# Power_Path.net
KiCad netlist of a schematic drawn in Altium Designer
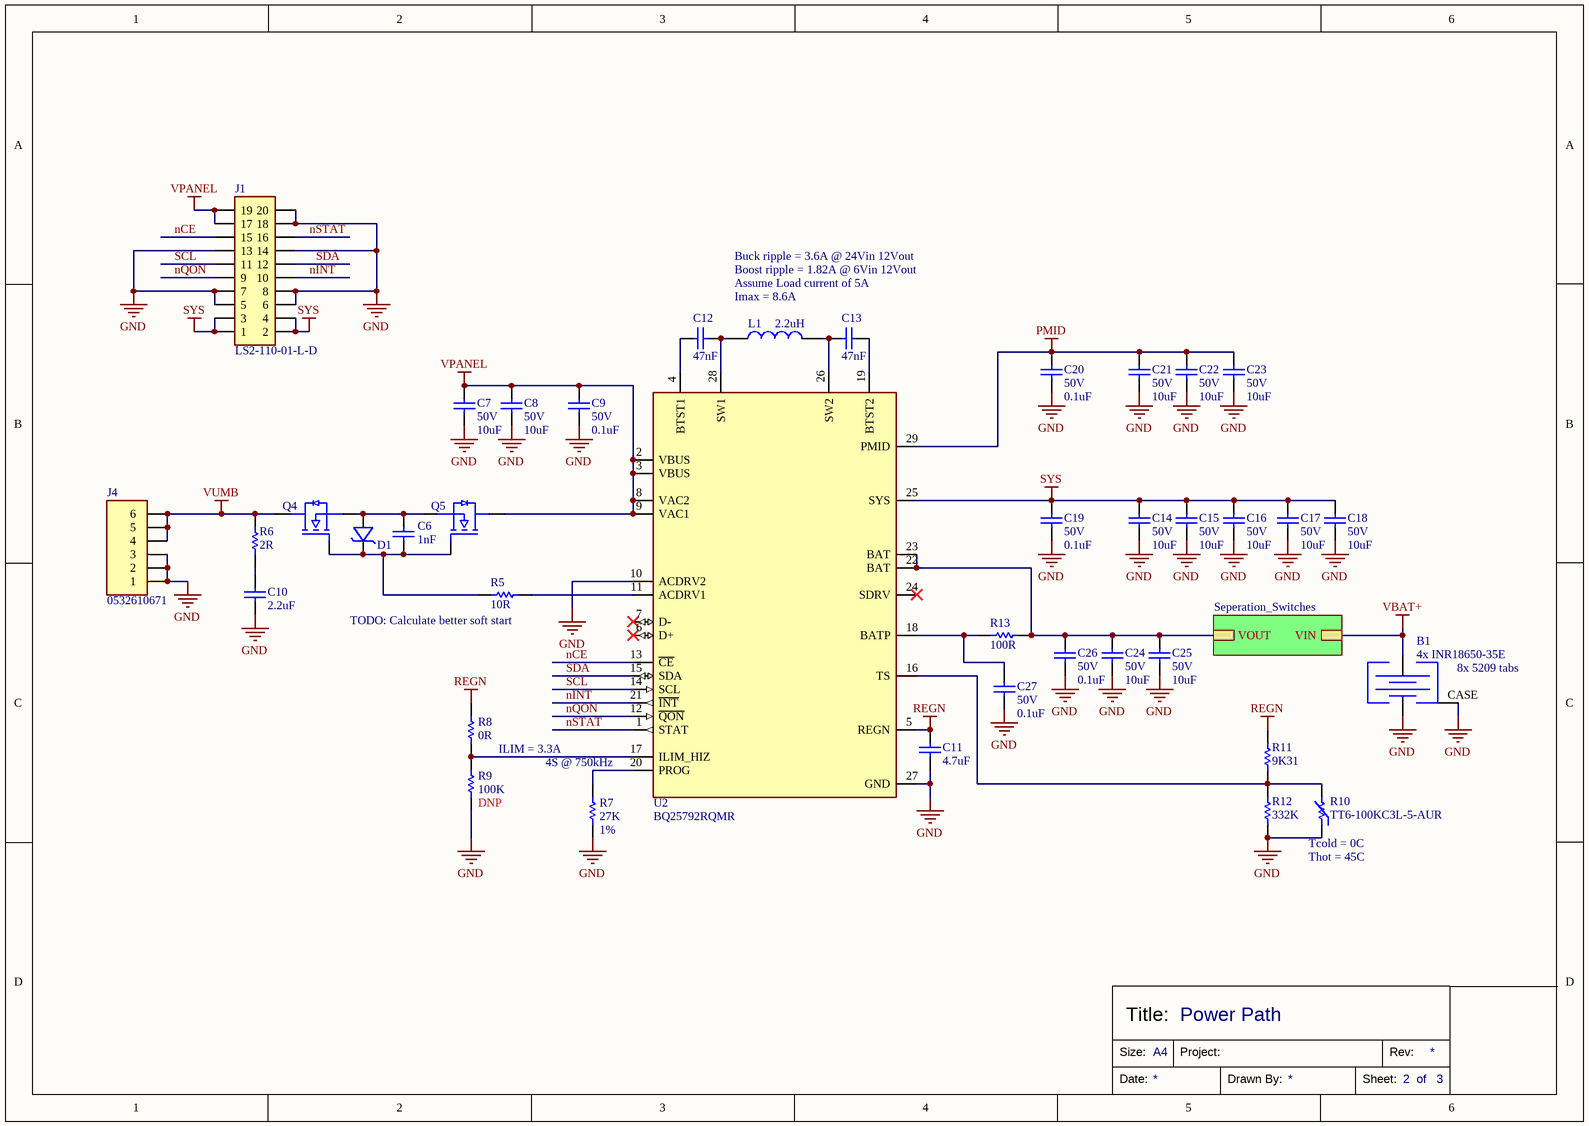
[diagram p0: Power_Path.SchDoc]

(export (version "E")
  (design (tool "Eeschema 10.0.6"))
  (components
    (comp (ref "B1")
      (value "4x INR18650-35E")
      (footprint "4S Battery")
      (description "Custom 4S battery component for Cubesat EPS")
      (libsource (lib "Ahristi_Library") (part "4S Battery"))
    )
    (comp (ref "C6")
      (value "GRM1885C1H102JA01D")
      (footprint "CAPC0603X040")
      (description "1nF ±5% 50V Ceramic Capacitor C0G, NP0 0603 (1608 Metric)")
      (fields
        (field (name "TOLERANCE") "5%")
        (field (name "DISTRIBUTOR PART NUMBER") "490-1451-1-ND")
        (field (name "CAPACITANCE") "1nF")
      )
      (libsource (lib "Ahristi_Library") (part "GRM1885C1H102JA01D"))
    )
    (comp (ref "C7")
      (value "CL32B106KBJNNNE")
      (footprint "CAPC1210X090")
      (description "10 µF ±10% 50V Ceramic Capacitor X7R 1210 (3225 Metric)")
      (fields
        (field (name "DISTRIBUTOR PART NUMBER") "1276-3387-1-ND")
        (field (name "TOLERANCE") "10%")
        (field (name "VOLTAGE RATING") "50V")
        (field (name "CAPACITANCE") "10uF")
      )
      (libsource (lib "Ahristi_Library") (part "CL32B106KBJNNNE"))
    )
    (comp (ref "C8")
      (value "CL32B106KBJNNNE")
      (footprint "CAPC1210X090")
      (description "10 µF ±10% 50V Ceramic Capacitor X7R 1210 (3225 Metric)")
      (fields
        (field (name "DISTRIBUTOR PART NUMBER") "1276-3387-1-ND")
        (field (name "TOLERANCE") "10%")
        (field (name "VOLTAGE RATING") "50V")
        (field (name "CAPACITANCE") "10uF")
      )
      (libsource (lib "Ahristi_Library") (part "CL32B106KBJNNNE"))
    )
    (comp (ref "C9")
      (value "CL05B104KB5NNNC")
      (footprint "CAPC0402X020")
      (description "0.1 µF ±10% 50V Ceramic Capacitor X7R 0402 (1005 Metric)")
      (fields
        (field (name "TOLERANCE") "10%")
        (field (name "DISTRIBUTOR PART NUMBER") "1276-CL05B104KB5NNNCCT-ND")
        (field (name "VOLTAGE RATING") "50V")
        (field (name "CAPACITANCE") "0.1uF")
      )
      (libsource (lib "Ahristi_Library") (part "CL05B104KB5NNNC"))
    )
    (comp (ref "C10")
      (value "CL21A225KBFNNNE")
      (footprint "CAPC0805X060")
      (description "2.2uF ±10% 25V Ceramic Capacitor X7R 0805 (2012 Metric)")
      (fields
        (field (name "DISTRIBUTOR PART NUMBER") "1276-6702-1-ND")
        (field (name "TOLERANCE") "10%")
        (field (name "CAPACITANCE") "2.2uF")
      )
      (libsource (lib "Ahristi_Library") (part "CL21A225KBFNNNE"))
    )
    (comp (ref "C11")
      (value "CL21A475KAQNNNE")
      (footprint "CAPC0805X060")
      (description "4.7 µF ±10% 25V Ceramic Capacitor X5R 0805 (2012 Metric)")
      (fields
        (field (name "DISTRIBUTOR PART NUMBER") "1276-1244-1-ND")
        (field (name "TOLERANCE") "10%")
        (field (name "CAPACITANCE") "4.7uF")
      )
      (libsource (lib "Ahristi_Library") (part "CL21A475KAQNNNE"))
    )
    (comp (ref "C12")
      (value "C0603C473K1RACTU")
      (footprint "CAPC0603X040")
      (description "0.047 µF ±10% 100V Ceramic Capacitor X7R 0603 (1608 Metric)")
      (fields
        (field (name "DISTRIBUTOR PART NUMBER") "399-C0603C473K1RACTUCT-ND")
        (field (name "TOLERANCE") "10%")
        (field (name "CAPACITANCE") "47nF")
      )
      (libsource (lib "Ahristi_Library") (part "C0603C473K1RACTU"))
    )
    (comp (ref "C13")
      (value "C0603C473K1RACTU")
      (footprint "CAPC0603X040")
      (description "0.047 µF ±10% 100V Ceramic Capacitor X7R 0603 (1608 Metric)")
      (fields
        (field (name "DISTRIBUTOR PART NUMBER") "399-C0603C473K1RACTUCT-ND")
        (field (name "TOLERANCE") "10%")
        (field (name "CAPACITANCE") "47nF")
      )
      (libsource (lib "Ahristi_Library") (part "C0603C473K1RACTU"))
    )
    (comp (ref "C14")
      (value "CL32B106KBJNNNE")
      (footprint "CAPC1210X090")
      (description "10 µF ±10% 50V Ceramic Capacitor X7R 1210 (3225 Metric)")
      (fields
        (field (name "DISTRIBUTOR PART NUMBER") "1276-3387-1-ND")
        (field (name "TOLERANCE") "10%")
        (field (name "VOLTAGE RATING") "50V")
        (field (name "CAPACITANCE") "10uF")
      )
      (libsource (lib "Ahristi_Library") (part "CL32B106KBJNNNE"))
    )
    (comp (ref "C15")
      (value "CL32B106KBJNNNE")
      (footprint "CAPC1210X090")
      (description "10 µF ±10% 50V Ceramic Capacitor X7R 1210 (3225 Metric)")
      (fields
        (field (name "DISTRIBUTOR PART NUMBER") "1276-3387-1-ND")
        (field (name "TOLERANCE") "10%")
        (field (name "VOLTAGE RATING") "50V")
        (field (name "CAPACITANCE") "10uF")
      )
      (libsource (lib "Ahristi_Library") (part "CL32B106KBJNNNE"))
    )
    (comp (ref "C16")
      (value "CL32B106KBJNNNE")
      (footprint "CAPC1210X090")
      (description "10 µF ±10% 50V Ceramic Capacitor X7R 1210 (3225 Metric)")
      (fields
        (field (name "DISTRIBUTOR PART NUMBER") "1276-3387-1-ND")
        (field (name "TOLERANCE") "10%")
        (field (name "VOLTAGE RATING") "50V")
        (field (name "CAPACITANCE") "10uF")
      )
      (libsource (lib "Ahristi_Library") (part "CL32B106KBJNNNE"))
    )
    (comp (ref "C17")
      (value "CL32B106KBJNNNE")
      (footprint "CAPC1210X090")
      (description "10 µF ±10% 50V Ceramic Capacitor X7R 1210 (3225 Metric)")
      (fields
        (field (name "DISTRIBUTOR PART NUMBER") "1276-3387-1-ND")
        (field (name "TOLERANCE") "10%")
        (field (name "VOLTAGE RATING") "50V")
        (field (name "CAPACITANCE") "10uF")
      )
      (libsource (lib "Ahristi_Library") (part "CL32B106KBJNNNE"))
    )
    (comp (ref "C18")
      (value "CL32B106KBJNNNE")
      (footprint "CAPC1210X090")
      (description "10 µF ±10% 50V Ceramic Capacitor X7R 1210 (3225 Metric)")
      (fields
        (field (name "DISTRIBUTOR PART NUMBER") "1276-3387-1-ND")
        (field (name "TOLERANCE") "10%")
        (field (name "VOLTAGE RATING") "50V")
        (field (name "CAPACITANCE") "10uF")
      )
      (libsource (lib "Ahristi_Library") (part "CL32B106KBJNNNE"))
    )
    (comp (ref "C19")
      (value "CL05B104KB5NNNC")
      (footprint "CAPC0402X020")
      (description "0.1 µF ±10% 50V Ceramic Capacitor X7R 0402 (1005 Metric)")
      (fields
        (field (name "TOLERANCE") "10%")
        (field (name "DISTRIBUTOR PART NUMBER") "1276-CL05B104KB5NNNCCT-ND")
        (field (name "VOLTAGE RATING") "50V")
        (field (name "CAPACITANCE") "0.1uF")
      )
      (libsource (lib "Ahristi_Library") (part "CL05B104KB5NNNC"))
    )
    (comp (ref "C20")
      (value "CL05B104KB5NNNC")
      (footprint "CAPC0402X020")
      (description "0.1 µF ±10% 50V Ceramic Capacitor X7R 0402 (1005 Metric)")
      (fields
        (field (name "TOLERANCE") "10%")
        (field (name "DISTRIBUTOR PART NUMBER") "1276-CL05B104KB5NNNCCT-ND")
        (field (name "VOLTAGE RATING") "50V")
        (field (name "CAPACITANCE") "0.1uF")
      )
      (libsource (lib "Ahristi_Library") (part "CL05B104KB5NNNC"))
    )
    (comp (ref "C21")
      (value "CL32B106KBJNNNE")
      (footprint "CAPC1210X090")
      (description "10 µF ±10% 50V Ceramic Capacitor X7R 1210 (3225 Metric)")
      (fields
        (field (name "DISTRIBUTOR PART NUMBER") "1276-3387-1-ND")
        (field (name "TOLERANCE") "10%")
        (field (name "VOLTAGE RATING") "50V")
        (field (name "CAPACITANCE") "10uF")
      )
      (libsource (lib "Ahristi_Library") (part "CL32B106KBJNNNE"))
    )
    (comp (ref "C22")
      (value "CL32B106KBJNNNE")
      (footprint "CAPC1210X090")
      (description "10 µF ±10% 50V Ceramic Capacitor X7R 1210 (3225 Metric)")
      (fields
        (field (name "DISTRIBUTOR PART NUMBER") "1276-3387-1-ND")
        (field (name "TOLERANCE") "10%")
        (field (name "VOLTAGE RATING") "50V")
        (field (name "CAPACITANCE") "10uF")
      )
      (libsource (lib "Ahristi_Library") (part "CL32B106KBJNNNE"))
    )
    (comp (ref "C23")
      (value "CL32B106KBJNNNE")
      (footprint "CAPC1210X090")
      (description "10 µF ±10% 50V Ceramic Capacitor X7R 1210 (3225 Metric)")
      (fields
        (field (name "DISTRIBUTOR PART NUMBER") "1276-3387-1-ND")
        (field (name "TOLERANCE") "10%")
        (field (name "VOLTAGE RATING") "50V")
        (field (name "CAPACITANCE") "10uF")
      )
      (libsource (lib "Ahristi_Library") (part "CL32B106KBJNNNE"))
    )
    (comp (ref "C24")
      (value "CL32B106KBJNNNE")
      (footprint "CAPC1210X090")
      (description "10 µF ±10% 50V Ceramic Capacitor X7R 1210 (3225 Metric)")
      (fields
        (field (name "DISTRIBUTOR PART NUMBER") "1276-3387-1-ND")
        (field (name "TOLERANCE") "10%")
        (field (name "VOLTAGE RATING") "50V")
        (field (name "CAPACITANCE") "10uF")
      )
      (libsource (lib "Ahristi_Library") (part "CL32B106KBJNNNE"))
    )
    (comp (ref "C25")
      (value "CL32B106KBJNNNE")
      (footprint "CAPC1210X090")
      (description "10 µF ±10% 50V Ceramic Capacitor X7R 1210 (3225 Metric)")
      (fields
        (field (name "DISTRIBUTOR PART NUMBER") "1276-3387-1-ND")
        (field (name "TOLERANCE") "10%")
        (field (name "VOLTAGE RATING") "50V")
        (field (name "CAPACITANCE") "10uF")
      )
      (libsource (lib "Ahristi_Library") (part "CL32B106KBJNNNE"))
    )
    (comp (ref "C26")
      (value "CL05B104KB5NNNC")
      (footprint "CAPC0402X020")
      (description "0.1 µF ±10% 50V Ceramic Capacitor X7R 0402 (1005 Metric)")
      (fields
        (field (name "TOLERANCE") "10%")
        (field (name "DISTRIBUTOR PART NUMBER") "1276-CL05B104KB5NNNCCT-ND")
        (field (name "VOLTAGE RATING") "50V")
        (field (name "CAPACITANCE") "0.1uF")
      )
      (libsource (lib "Ahristi_Library") (part "CL05B104KB5NNNC"))
    )
    (comp (ref "C27")
      (value "CL05B104KB5NNNC")
      (footprint "CAPC0402X020")
      (description "0.1 µF ±10% 50V Ceramic Capacitor X7R 0402 (1005 Metric)")
      (fields
        (field (name "TOLERANCE") "10%")
        (field (name "DISTRIBUTOR PART NUMBER") "1276-CL05B104KB5NNNCCT-ND")
        (field (name "VOLTAGE RATING") "50V")
        (field (name "CAPACITANCE") "0.1uF")
      )
      (libsource (lib "Ahristi_Library") (part "CL05B104KB5NNNC"))
    )
    (comp (ref "D1")
      (value "BZT52C12T-7")
      (footprint "SOD-523")
      (description "Zener Diode 12 V 300 mW ±5% Surface Mount SOD-523")
      (fields (field (name "DISTRIBUTOR PART NUMBER") "BZT52C12T-7DICT-ND"))
      (libsource (lib "Ahristi_Library") (part "BZT52C12T-7"))
    )
    (comp (ref "J1")
      (value "LS2-110-01-L-D")
      (footprint "LS2-110-01-L-D")
      (description "Connector Self Mating 20 Position , Non-Gendered, Hermaphroditic Through Hole Gold")
      (fields (field (name "DISTRIBUTOR PART NUMBER") "SAM9665-ND"))
      (libsource (lib "Ahristi_Library") (part "LS2-110-01-L-D"))
    )
    (comp (ref "J4")
      (value "0532610671")
      (footprint "0532610671")
      (description "Connector Header Surface Mount, Right Angle 6 position 0.049\" (1.25mm) Picoblade")
      (fields (field (name "DISTRIBUTOR PART NUMBER") "WM7624CT-ND"))
      (libsource (lib "Ahristi_Library") (part "0532610671"))
    )
    (comp (ref "L1")
      (value "SPM7054VT-2R2M-D")
      (footprint "SPM7054VT-2R2M-D")
      (description "2.2 µH Shielded Drum Core, Wirewound Inductor 12 A 7.4mOhm Nonstandard")
      (fields
        (field (name "DISTRIBUTOR PART NUMBER") "445-SPM7054VT-2R2M-DCT-ND")
        (field (name "INDUCTANCE") "2.2uH")
        (field (name "TOLERANCE") "20%")
      )
      (libsource (lib "Ahristi_Library") (part "SPM7054VT-2R2M-D"))
    )
    (comp (ref "Q4")
      (value "CSD18511Q5A")
      (footprint "CSD18511Q5A")
      (description "40-V, N channel NexFET™ power MOSFET, single SON 5 mm x 6 mm, 2.3 mOhm")
      (fields (field (name "DISTRIBUTOR PART NUMBER") "296-48119-1-ND"))
      (libsource (lib "Ahristi_Library") (part "CSD18511Q5A"))
    )
    (comp (ref "Q5")
      (value "CSD18511Q5A")
      (footprint "CSD18511Q5A")
      (description "40-V, N channel NexFET™ power MOSFET, single SON 5 mm x 6 mm, 2.3 mOhm")
      (fields (field (name "DISTRIBUTOR PART NUMBER") "296-48119-1-ND"))
      (libsource (lib "Ahristi_Library") (part "CSD18511Q5A"))
    )
    (comp (ref "R5")
      (value "RMCF0603FT10R0")
      (footprint "RESC0603")
      (description "10 Ohms ±1% 0.1W, 1/10W Chip Resistor 0603 (1608 Metric) Automotive AEC-Q200 Thick Film")
      (fields
        (field (name "TOLERANCE") "1%")
        (field (name "DISTRIBUTOR PART NUMBER") "RMCF0603FT10R0CT-ND")
        (field (name "RESISTANCE") "10R")
      )
      (libsource (lib "Ahristi_Library") (part "RMCF0603FT10R0"))
    )
    (comp (ref "R6")
      (value "RMCF0603FT2R00")
      (footprint "RESC0603")
      (fields
        (field (name "TOLERANCE") "1%")
        (field (name "DISTRIBUTOR PART NUMBER") "RMCF0603FT2R00CT-ND")
        (field (name "RESISTANCE") "2R")
      )
      (libsource (lib "Ahristi_Library") (part "RMCF0603FT2R00"))
    )
    (comp (ref "R7")
      (value "RMCF0603FT27K0")
      (footprint "RESC0603")
      (description "27 kOhms ±1% 0.1W, 1/10W Chip Resistor 0603 (1608 Metric) Automotive AEC-Q200 Thick Film")
      (fields
        (field (name "TOLERANCE") "1%")
        (field (name "DISTRIBUTOR PART NUMBER") "RMCF0603FT27K0CT-ND")
        (field (name "RESISTANCE") "27K")
      )
      (libsource (lib "Ahristi_Library") (part "RMCF0603FT27K0"))
    )
    (comp (ref "R8")
      (value "RMCF0805ZT0R00")
      (footprint "RESC0805")
      (description "0 Ohms Jumper Chip Resistor 0805 (2012 Metric) Automotive AEC-Q200 Thick Film")
      (fields
        (field (name "TOLERANCE") "1%")
        (field (name "DISTRIBUTOR PART NUMBER") "RMCF0805ZT0R00CT-ND")
        (field (name "RESISTANCE") "0R")
      )
      (libsource (lib "Ahristi_Library") (part "RMCF0805ZT0R00"))
    )
    (comp (ref "R9")
      (value "RMCF0805FG100K")
      (footprint "RESC0805")
      (description "100 kOhms ±1% 0.125W, 1/8W Chip Resistor 0805 (2012 Metric) Automotive AEC-Q200 Thick Film")
      (fields
        (field (name "TOLERANCE") "1%")
        (field (name "DISTRIBUTOR PART NUMBER") "RMCF0805FG100KCT-ND")
        (field (name "RESISTANCE") "100K")
      )
      (libsource (lib "Ahristi_Library") (part "RMCF0805FG100K"))
    )
    (comp (ref "R10")
      (value "TT6-100KC3L-5-AUR")
      (footprint "TT6-10KC8-9-25")
      (description "NTC Thermistor 10k Probe")
      (fields (field (name "DISTRIBUTOR PART NUMBER") "1912-TT6-10KC8-9-25-ND"))
      (libsource (lib "Ahristi_Library") (part "TT6-100KC3L-5-AUR"))
    )
    (comp (ref "R11")
      (value "RMCF0805FT9K31")
      (footprint "RESC0805")
      (description "9.31 kOhms ±1% 0.125W, 1/8W Chip Resistor 0805 (2012 Metric) Automotive AEC-Q200 Thick Film")
      (fields
        (field (name "TOLERANCE") "1%")
        (field (name "DISTRIBUTOR PART NUMBER") "738-RMCF0805FT9K31CT-ND")
        (field (name "RESISTANCE") "9K31")
      )
      (libsource (lib "Ahristi_Library") (part "RMCF0805FT9K31"))
    )
    (comp (ref "R12")
      (value "RMCF0805FT332K")
      (footprint "RESC0805")
      (description "332 kOhms ±1% 0.125W, 1/8W Chip Resistor 0805 (2012 Metric) Automotive AEC-Q200 Thick Film")
      (fields
        (field (name "TOLERANCE") "1%")
        (field (name "DISTRIBUTOR PART NUMBER") "RMCF0805FT332KCT-ND")
        (field (name "RESISTANCE") "332K")
      )
      (libsource (lib "Ahristi_Library") (part "RMCF0805FT332K"))
    )
    (comp (ref "R13")
      (value "RMCF0805FT100R")
      (footprint "RESC0805")
      (description "100 Ohms ±1% 0.125W, 1/8W Chip Resistor 0805 (2012 Metric) Automotive AEC-Q200 Thick Film")
      (fields
        (field (name "TOLERANCE") "1%")
        (field (name "DISTRIBUTOR PART NUMBER") "RMCF0805FT100RCT-ND")
        (field (name "RESISTANCE") "100R")
      )
      (libsource (lib "Ahristi_Library") (part "RMCF0805FT100R"))
    )
    (comp (ref "U2")
      (value "BQ25792RQMR")
      (footprint "BQ25792RQMR")
      (fields (field (name "DISTRIBUTOR PART NUMBER") "296-BQ25792RQMRCT-ND"))
      (libsource (lib "Ahristi_Library") (part "BQ25792RQMR"))
    )
  )
  (nets
    (net (code "1") (name "/SCL") (class "Default")
      (node (ref "J1") (pin "11") (pinfunction "11_11") (pintype "passive"))
      (node (ref "U2") (pin "14") (pinfunction "SCL_14") (pintype "input"))
    )
    (net (code "2") (name "/SDA") (class "Default")
      (node (ref "J1") (pin "12") (pinfunction "12_12") (pintype "passive"))
      (node (ref "U2") (pin "15") (pinfunction "SDA_15") (pintype "bidirectional"))
    )
    (net (code "3") (name "/VOUT") (class "Default")
      (node (ref "C24") (pin "2") (pinfunction "2_2") (pintype "passive"))
      (node (ref "C25") (pin "2") (pinfunction "2_2") (pintype "passive"))
      (node (ref "C26") (pin "2") (pinfunction "2_2") (pintype "passive"))
      (node (ref "R13") (pin "2") (pinfunction "2_2") (pintype "passive"))
      (node (ref "U2") (pin "22") (pinfunction "BAT_22") (pintype "passive"))
      (node (ref "U2") (pin "23") (pinfunction "BAT_23") (pintype "passive"))
    )
    (net (code "4") (name "/nCE") (class "Default")
      (node (ref "J1") (pin "15") (pinfunction "15_15") (pintype "passive"))
      (node (ref "U2") (pin "13") (pinfunction "~{CE}_13") (pintype "passive"))
    )
    (net (code "5") (name "/nINT") (class "Default")
      (node (ref "J1") (pin "10") (pinfunction "10_10") (pintype "passive"))
      (node (ref "U2") (pin "21") (pinfunction "~{INT}_21") (pintype "output"))
    )
    (net (code "6") (name "/nQON") (class "Default")
      (node (ref "J1") (pin "9") (pinfunction "9_9") (pintype "passive"))
      (node (ref "U2") (pin "12") (pinfunction "~{QON}_12") (pintype "input"))
    )
    (net (code "7") (name "/nSTAT") (class "Default")
      (node (ref "J1") (pin "16") (pinfunction "16_16") (pintype "passive"))
      (node (ref "U2") (pin "1") (pinfunction "STAT_1") (pintype "output"))
    )
    (net (code "8") (name "GND") (class "Default")
      (node (ref "B1") (pin "1") (pinfunction "1_1") (pintype "passive"))
      (node (ref "B1") (pin "CASE") (pinfunction "CASE_CASE") (pintype "passive"))
      (node (ref "C10") (pin "1") (pinfunction "1_1") (pintype "passive"))
      (node (ref "C11") (pin "1") (pinfunction "1_1") (pintype "passive"))
      (node (ref "C14") (pin "1") (pinfunction "1_1") (pintype "passive"))
      (node (ref "C15") (pin "1") (pinfunction "1_1") (pintype "passive"))
      (node (ref "C16") (pin "1") (pinfunction "1_1") (pintype "passive"))
      (node (ref "C17") (pin "1") (pinfunction "1_1") (pintype "passive"))
      (node (ref "C18") (pin "1") (pinfunction "1_1") (pintype "passive"))
      (node (ref "C19") (pin "1") (pinfunction "1_1") (pintype "passive"))
      (node (ref "C20") (pin "1") (pinfunction "1_1") (pintype "passive"))
      (node (ref "C21") (pin "1") (pinfunction "1_1") (pintype "passive"))
      (node (ref "C22") (pin "1") (pinfunction "1_1") (pintype "passive"))
      (node (ref "C23") (pin "1") (pinfunction "1_1") (pintype "passive"))
      (node (ref "C24") (pin "1") (pinfunction "1_1") (pintype "passive"))
      (node (ref "C25") (pin "1") (pinfunction "1_1") (pintype "passive"))
      (node (ref "C26") (pin "1") (pinfunction "1_1") (pintype "passive"))
      (node (ref "C27") (pin "1") (pinfunction "1_1") (pintype "passive"))
      (node (ref "C7") (pin "1") (pinfunction "1_1") (pintype "passive"))
      (node (ref "C8") (pin "1") (pinfunction "1_1") (pintype "passive"))
      (node (ref "C9") (pin "1") (pinfunction "1_1") (pintype "passive"))
      (node (ref "J1") (pin "13") (pinfunction "13_13") (pintype "passive"))
      (node (ref "J1") (pin "14") (pinfunction "14_14") (pintype "passive"))
      (node (ref "J1") (pin "18") (pinfunction "18_18") (pintype "passive"))
      (node (ref "J1") (pin "20") (pinfunction "20_20") (pintype "passive"))
      (node (ref "J1") (pin "5") (pinfunction "5_5") (pintype "passive"))
      (node (ref "J1") (pin "6") (pinfunction "6_6") (pintype "passive"))
      (node (ref "J1") (pin "7") (pinfunction "7_7") (pintype "passive"))
      (node (ref "J1") (pin "8") (pinfunction "8_8") (pintype "passive"))
      (node (ref "J4") (pin "1") (pinfunction "1_1") (pintype "passive"))
      (node (ref "J4") (pin "2") (pinfunction "2_2") (pintype "passive"))
      (node (ref "J4") (pin "3") (pinfunction "3_3") (pintype "passive"))
      (node (ref "R10") (pin "1") (pinfunction "1_1") (pintype "passive"))
      (node (ref "R12") (pin "1") (pinfunction "1_1") (pintype "passive"))
      (node (ref "R7") (pin "1") (pinfunction "1_1") (pintype "passive"))
      (node (ref "R9") (pin "1") (pinfunction "1_1") (pintype "passive"))
      (node (ref "U2") (pin "10") (pinfunction "ACDRV2_10") (pintype "passive"))
      (node (ref "U2") (pin "27") (pinfunction "GND_27") (pintype "passive"))
    )
    (net (code "9") (name "Net-(C10-Pad2)") (class "Default")
      (node (ref "C10") (pin "2") (pinfunction "2_2") (pintype "passive"))
      (node (ref "R6") (pin "1") (pinfunction "1_1") (pintype "passive"))
    )
    (net (code "10") (name "Net-(Q4-G)") (class "Default")
      (node (ref "C6") (pin "1") (pinfunction "1_1") (pintype "passive"))
      (node (ref "D1") (pin "K") (pinfunction "K_K") (pintype "passive"))
      (node (ref "Q4") (pin "1") (pinfunction "G_1") (pintype "passive"))
      (node (ref "Q5") (pin "1") (pinfunction "G_1") (pintype "passive"))
      (node (ref "R5") (pin "1") (pinfunction "1_1") (pintype "passive"))
    )
    (net (code "11") (name "Net-(Q4-S)") (class "Default")
      (node (ref "C6") (pin "2") (pinfunction "2_2") (pintype "passive"))
      (node (ref "D1") (pin "A") (pinfunction "A_A") (pintype "passive"))
      (node (ref "Q4") (pin "3") (pinfunction "S_3") (pintype "passive"))
      (node (ref "Q5") (pin "3") (pinfunction "S_3") (pintype "passive"))
    )
    (net (code "12") (name "Net-(U2-ACDRV1)") (class "Default")
      (node (ref "R5") (pin "2") (pinfunction "2_2") (pintype "passive"))
      (node (ref "U2") (pin "11") (pinfunction "ACDRV1_11") (pintype "passive"))
    )
    (net (code "13") (name "Net-(U2-BATP)") (class "Default")
      (node (ref "C27") (pin "2") (pinfunction "2_2") (pintype "passive"))
      (node (ref "R13") (pin "1") (pinfunction "1_1") (pintype "passive"))
      (node (ref "U2") (pin "18") (pinfunction "BATP_18") (pintype "passive"))
    )
    (net (code "14") (name "Net-(U2-BTST1)") (class "Default")
      (node (ref "C12") (pin "1") (pinfunction "1_1") (pintype "passive"))
      (node (ref "U2") (pin "4") (pinfunction "BTST1_4") (pintype "passive"))
    )
    (net (code "15") (name "Net-(U2-BTST2)") (class "Default")
      (node (ref "C13") (pin "2") (pinfunction "2_2") (pintype "passive"))
      (node (ref "U2") (pin "19") (pinfunction "BTST2_19") (pintype "passive"))
    )
    (net (code "16") (name "Net-(U2-ILIM_HIZ)") (class "Default")
      (node (ref "R8") (pin "1") (pinfunction "1_1") (pintype "passive"))
      (node (ref "R9") (pin "2") (pinfunction "2_2") (pintype "passive"))
      (node (ref "U2") (pin "17") (pinfunction "ILIM_HIZ_17") (pintype "passive"))
    )
    (net (code "17") (name "Net-(U2-PROG)") (class "Default")
      (node (ref "R7") (pin "2") (pinfunction "2_2") (pintype "passive"))
      (node (ref "U2") (pin "20") (pinfunction "PROG_20") (pintype "passive"))
    )
    (net (code "18") (name "Net-(U2-SW1)") (class "Default")
      (node (ref "C12") (pin "2") (pinfunction "2_2") (pintype "passive"))
      (node (ref "L1") (pin "1") (pinfunction "1_1") (pintype "passive"))
      (node (ref "U2") (pin "28") (pinfunction "SW1_28") (pintype "passive"))
    )
    (net (code "19") (name "Net-(U2-SW2)") (class "Default")
      (node (ref "C13") (pin "1") (pinfunction "1_1") (pintype "passive"))
      (node (ref "L1") (pin "2") (pinfunction "2_2") (pintype "passive"))
      (node (ref "U2") (pin "26") (pinfunction "SW2_26") (pintype "passive"))
    )
    (net (code "20") (name "Net-(U2-TS)") (class "Default")
      (node (ref "R10") (pin "2") (pinfunction "2_2") (pintype "passive"))
      (node (ref "R11") (pin "1") (pinfunction "1_1") (pintype "passive"))
      (node (ref "R12") (pin "2") (pinfunction "2_2") (pintype "passive"))
      (node (ref "U2") (pin "16") (pinfunction "TS_16") (pintype "passive"))
    )
    (net (code "21") (name "PMID") (class "Default")
      (node (ref "C20") (pin "2") (pinfunction "2_2") (pintype "passive"))
      (node (ref "C21") (pin "2") (pinfunction "2_2") (pintype "passive"))
      (node (ref "C22") (pin "2") (pinfunction "2_2") (pintype "passive"))
      (node (ref "C23") (pin "2") (pinfunction "2_2") (pintype "passive"))
      (node (ref "U2") (pin "29") (pinfunction "PMID_29") (pintype "passive"))
    )
    (net (code "22") (name "REGN") (class "Default")
      (node (ref "C11") (pin "2") (pinfunction "2_2") (pintype "passive"))
      (node (ref "R11") (pin "2") (pinfunction "2_2") (pintype "passive"))
      (node (ref "R8") (pin "2") (pinfunction "2_2") (pintype "passive"))
      (node (ref "U2") (pin "5") (pinfunction "REGN_5") (pintype "passive"))
    )
    (net (code "23") (name "SYS") (class "Default")
      (node (ref "C14") (pin "2") (pinfunction "2_2") (pintype "passive"))
      (node (ref "C15") (pin "2") (pinfunction "2_2") (pintype "passive"))
      (node (ref "C16") (pin "2") (pinfunction "2_2") (pintype "passive"))
      (node (ref "C17") (pin "2") (pinfunction "2_2") (pintype "passive"))
      (node (ref "C18") (pin "2") (pinfunction "2_2") (pintype "passive"))
      (node (ref "C19") (pin "2") (pinfunction "2_2") (pintype "passive"))
      (node (ref "J1") (pin "1") (pinfunction "1_1") (pintype "passive"))
      (node (ref "J1") (pin "2") (pinfunction "2_2") (pintype "passive"))
      (node (ref "J1") (pin "3") (pinfunction "3_3") (pintype "passive"))
      (node (ref "J1") (pin "4") (pinfunction "4_4") (pintype "passive"))
      (node (ref "U2") (pin "25") (pinfunction "SYS_25") (pintype "passive"))
    )
    (net (code "24") (name "VBAT+") (class "Default")
      (node (ref "B1") (pin "2") (pinfunction "2_2") (pintype "passive"))
    )
    (net (code "25") (name "VPANEL") (class "Default")
      (node (ref "C7") (pin "2") (pinfunction "2_2") (pintype "passive"))
      (node (ref "C8") (pin "2") (pinfunction "2_2") (pintype "passive"))
      (node (ref "C9") (pin "2") (pinfunction "2_2") (pintype "passive"))
      (node (ref "J1") (pin "17") (pinfunction "17_17") (pintype "passive"))
      (node (ref "J1") (pin "19") (pinfunction "19_19") (pintype "passive"))
      (node (ref "Q5") (pin "2") (pinfunction "D_2") (pintype "passive"))
      (node (ref "U2") (pin "2") (pinfunction "VBUS_2") (pintype "passive"))
      (node (ref "U2") (pin "3") (pinfunction "VBUS_3") (pintype "passive"))
      (node (ref "U2") (pin "8") (pinfunction "VAC2_8") (pintype "passive"))
      (node (ref "U2") (pin "9") (pinfunction "VAC1_9") (pintype "passive"))
    )
    (net (code "26") (name "VUMB") (class "Default")
      (node (ref "J4") (pin "4") (pinfunction "4_4") (pintype "passive"))
      (node (ref "J4") (pin "5") (pinfunction "5_5") (pintype "passive"))
      (node (ref "J4") (pin "6") (pinfunction "6_6") (pintype "passive"))
      (node (ref "Q4") (pin "2") (pinfunction "D_2") (pintype "passive"))
      (node (ref "R6") (pin "2") (pinfunction "2_2") (pintype "passive"))
    )
    (net (code "27") (name "unconnected-(U2-D+-Pad6)") (class "Default")
      (node (ref "U2") (pin "6") (pinfunction "D+_6") (pintype "bidirectional+no_connect"))
    )
    (net (code "28") (name "unconnected-(U2-D--Pad7)") (class "Default")
      (node (ref "U2") (pin "7") (pinfunction "D-_7") (pintype "bidirectional+no_connect"))
    )
    (net (code "29") (name "unconnected-(U2-SDRV-Pad24)") (class "Default")
      (node (ref "U2") (pin "24") (pinfunction "SDRV_24") (pintype "passive+no_connect"))
    )
  )
)
